# VGA_driver.net
KiCad netlist of a schematic drawn in Altium Designer
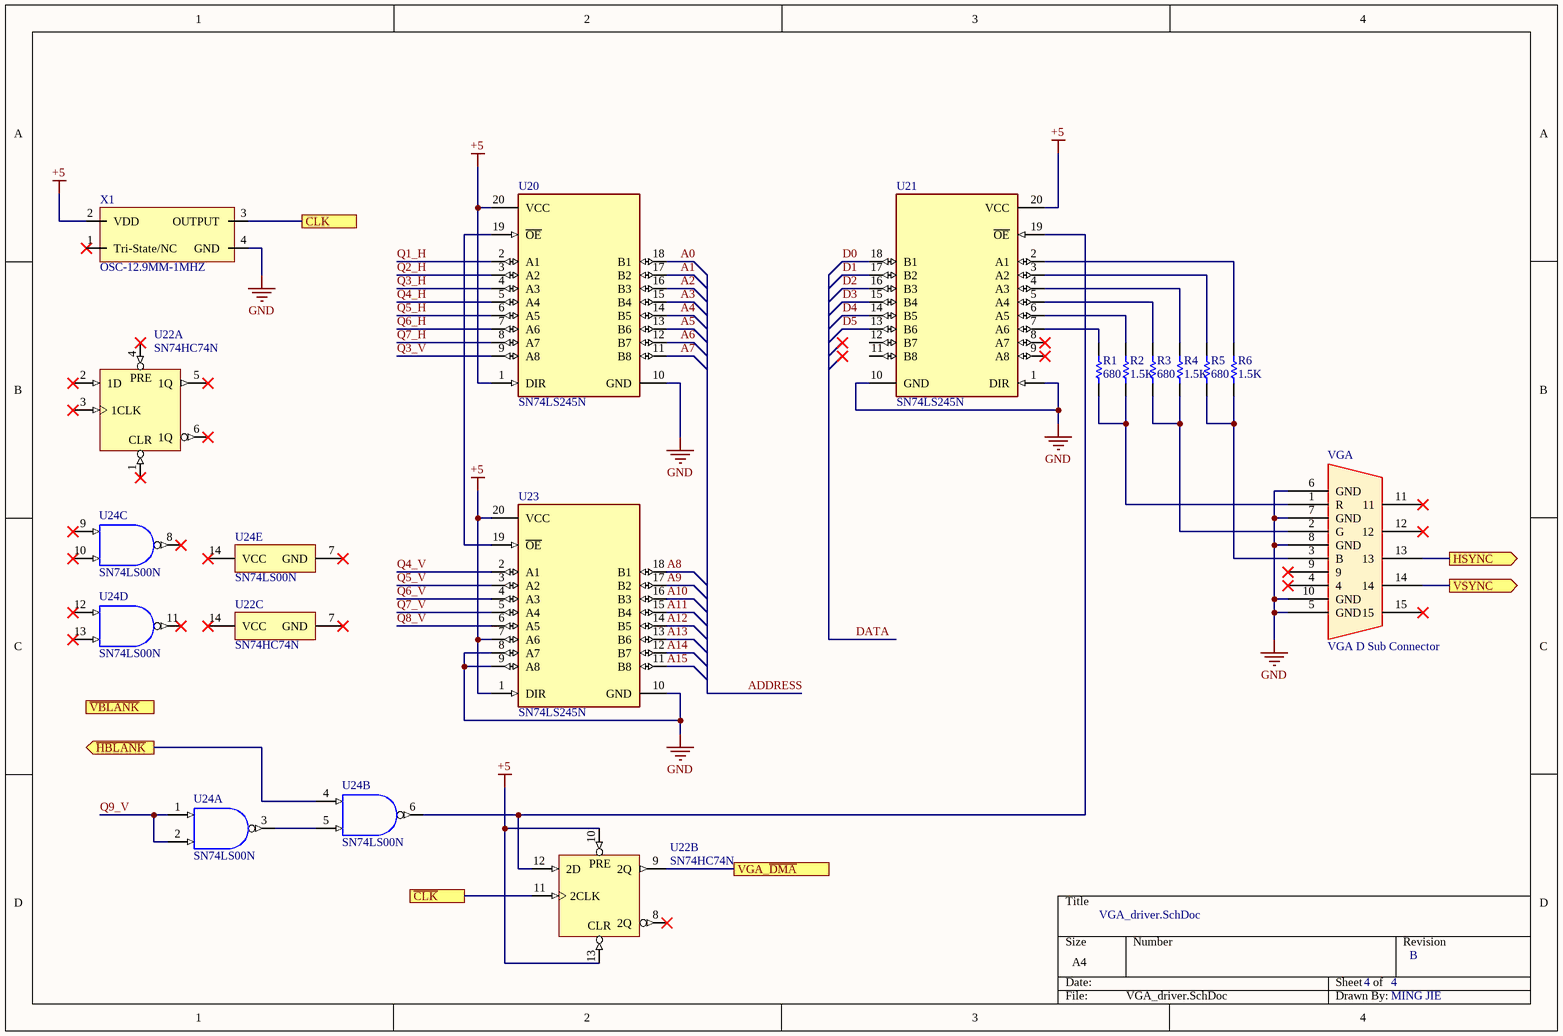
[diagram p0: VGA_driver.SchDoc]

(export (version "E")
  (design (tool "Eeschema 10.0.6"))
  (components
    (comp (ref "R1")
      (value "CRCW0805680RFKEA")
      (footprint "RESC2013X50X30NL20T20")
      (fields (field (name "MANUFACTURER") "Vishay Dale") (field (name "RESISTANCE") "680"))
      (libsource (lib "Altium Content Vault") (part "RES"))
    )
    (comp (ref "R2")
      (value "RC0805FR-071K5L")
      (footprint "RESC2013X60X35LL10T20")
      (description "RES 1.50K OHM 1/8W 1% 0805 SMD")
      (fields (field (name "MANUFACTURER") "Yageo") (field (name "RESISTANCE") "1.5K"))
      (libsource (lib "Altium Content Vault") (part "RES-2"))
    )
    (comp (ref "R3")
      (value "CRCW0805680RFKEA")
      (footprint "RESC2013X50X30NL20T20")
      (fields (field (name "MANUFACTURER") "Vishay Dale") (field (name "RESISTANCE") "680"))
      (libsource (lib "Altium Content Vault") (part "RES"))
    )
    (comp (ref "R4")
      (value "RC0805FR-071K5L")
      (footprint "RESC2013X60X35LL10T20")
      (description "RES 1.50K OHM 1/8W 1% 0805 SMD")
      (fields (field (name "MANUFACTURER") "Yageo") (field (name "RESISTANCE") "1.5K"))
      (libsource (lib "Altium Content Vault") (part "RES-2"))
    )
    (comp (ref "R5")
      (value "CRCW0805680RFKEA")
      (footprint "RESC2013X50X30NL20T20")
      (fields (field (name "MANUFACTURER") "Vishay Dale") (field (name "RESISTANCE") "680"))
      (libsource (lib "Altium Content Vault") (part "RES"))
    )
    (comp (ref "R6")
      (value "RC0805FR-071K5L")
      (footprint "RESC2013X60X35LL10T20")
      (description "RES 1.50K OHM 1/8W 1% 0805 SMD")
      (fields (field (name "MANUFACTURER") "Yageo") (field (name "RESISTANCE") "1.5K"))
      (libsource (lib "Altium Content Vault") (part "RES-2"))
    )
    (comp (ref "U20")
      (value "SN74LS245N")
      (footprint "FP-N0020A-MFG")
      (description "IC TXRX NON-INVERT 5.25V 20DIP")
      (libsource (lib "Altium Content Vault") (part "10c8780e4db4806136f4ae6e668cc9c"))
    )
    (comp (ref "U21")
      (value "SN74LS245N")
      (footprint "FP-N0020A-MFG")
      (description "IC TXRX NON-INVERT 5.25V 20DIP")
      (libsource (lib "") (part "10c8780e4db4806136f4ae6e668cc9c_1"))
    )
    (comp (ref "U22")
      (value "SN74HC74N")
      (footprint "N0014A")
      (description "Dual D-Type Positive-Edge-Triggered Flip-Flops With Clear and Preset, N0014A, TUBE")
      (fields
        (field (name "MANUFACTURER") "Texas Instruments")
        (field (name "GENERIC PART NUMBER") "SN74HC74")
      )
      (libsource (lib "Altium Content Vault") (part "TI-CD_SNX4XXXX74X-14"))
    )
    (comp (ref "U23")
      (value "SN74LS245N")
      (footprint "FP-N0020A-MFG")
      (description "IC TXRX NON-INVERT 5.25V 20DIP")
      (libsource (lib "Altium Content Vault") (part "10c8780e4db4806136f4ae6e668cc9c"))
    )
    (comp (ref "U24")
      (value "SN74LS00N")
      (footprint "N0014A")
      (description "Quad 2-input positive-NAND gates, N0014A, TUBE")
      (fields
        (field (name "MANUFACTURER") "Texas Instruments")
        (field (name "GENERIC PART NUMBER") "SN74LS00")
      )
      (libsource (lib "Altium Content Vault") (part "TI-NAND-4-2IN-14_G"))
    )
    (comp (ref "VGA")
      (value "VGA D Sub Connector")
      (footprint "VGA")
      (libsource (lib "6502_lib") (part "VGA-002"))
    )
    (comp (ref "X1")
      (value "OSC-12.9MM-1MHZ")
      (footprint "OSC_THT_12-9MM")
      (description "12.9MM x 12.9MM, 1MHz Can Oscillator")
      (libsource (lib "6502_lib") (part "OSC-12.9MM-1MHZ"))
    )
  )
  (nets
    (net (code "3") (name "+5") (class "Default")
      (node (ref "U20") (pin "1") (pinfunction "DIR_1") (pintype "input"))
      (node (ref "U20") (pin "20") (pinfunction "VCC_20") (pintype "power_in"))
      (node (ref "U21") (pin "20") (pinfunction "VCC_20") (pintype "power_in"))
      (node (ref "U22") (pin "10") (pinfunction "2~{PRE}_10") (pintype "input"))
      (node (ref "U22") (pin "13") (pinfunction "2~{CLR}_13") (pintype "input"))
      (node (ref "U23") (pin "1") (pinfunction "DIR_1") (pintype "input"))
      (node (ref "U23") (pin "20") (pinfunction "VCC_20") (pintype "power_in"))
      (node (ref "U23") (pin "7") (pinfunction "A6_7") (pintype "bidirectional"))
      (node (ref "X1") (pin "2") (pinfunction "VDD_2") (pintype "passive"))
    )
    (net (code "4") (name "/A0") (class "Default")
      (node (ref "U20") (pin "18") (pinfunction "B1_18") (pintype "bidirectional"))
    )
    (net (code "5") (name "/A1") (class "Default")
      (node (ref "U20") (pin "17") (pinfunction "B2_17") (pintype "bidirectional"))
    )
    (net (code "6") (name "/A2") (class "Default")
      (node (ref "U20") (pin "16") (pinfunction "B3_16") (pintype "bidirectional"))
    )
    (net (code "7") (name "/A3") (class "Default")
      (node (ref "U20") (pin "15") (pinfunction "B4_15") (pintype "bidirectional"))
    )
    (net (code "8") (name "/A4") (class "Default")
      (node (ref "U20") (pin "14") (pinfunction "B5_14") (pintype "bidirectional"))
    )
    (net (code "9") (name "/A5") (class "Default")
      (node (ref "U20") (pin "13") (pinfunction "B6_13") (pintype "bidirectional"))
    )
    (net (code "10") (name "/A6") (class "Default")
      (node (ref "U20") (pin "12") (pinfunction "B7_12") (pintype "bidirectional"))
    )
    (net (code "11") (name "/A7") (class "Default")
      (node (ref "U20") (pin "11") (pinfunction "B8_11") (pintype "bidirectional"))
    )
    (net (code "12") (name "/A8") (class "Default")
      (node (ref "U23") (pin "18") (pinfunction "B1_18") (pintype "bidirectional"))
    )
    (net (code "13") (name "/A9") (class "Default")
      (node (ref "U23") (pin "17") (pinfunction "B2_17") (pintype "bidirectional"))
    )
    (net (code "14") (name "/A10") (class "Default")
      (node (ref "U23") (pin "16") (pinfunction "B3_16") (pintype "bidirectional"))
    )
    (net (code "15") (name "/A11") (class "Default")
      (node (ref "U23") (pin "15") (pinfunction "B4_15") (pintype "bidirectional"))
    )
    (net (code "16") (name "/A12") (class "Default")
      (node (ref "U23") (pin "14") (pinfunction "B5_14") (pintype "bidirectional"))
    )
    (net (code "17") (name "/A13") (class "Default")
      (node (ref "U23") (pin "13") (pinfunction "B6_13") (pintype "bidirectional"))
    )
    (net (code "18") (name "/A14") (class "Default")
      (node (ref "U23") (pin "12") (pinfunction "B7_12") (pintype "bidirectional"))
    )
    (net (code "19") (name "/A15") (class "Default")
      (node (ref "U23") (pin "11") (pinfunction "B8_11") (pintype "bidirectional"))
    )
    (net (code "20") (name "/CLK") (class "Default")
      (node (ref "X1") (pin "3") (pinfunction "OUTPUT_3") (pintype "passive"))
    )
    (net (code "21") (name "/D0") (class "Default")
      (node (ref "U21") (pin "18") (pinfunction "B1_18") (pintype "bidirectional"))
    )
    (net (code "22") (name "/D1") (class "Default")
      (node (ref "U21") (pin "17") (pinfunction "B2_17") (pintype "bidirectional"))
    )
    (net (code "23") (name "/D2") (class "Default")
      (node (ref "U21") (pin "16") (pinfunction "B3_16") (pintype "bidirectional"))
    )
    (net (code "24") (name "/D3") (class "Default")
      (node (ref "U21") (pin "15") (pinfunction "B4_15") (pintype "bidirectional"))
    )
    (net (code "25") (name "/D4") (class "Default")
      (node (ref "U21") (pin "14") (pinfunction "B5_14") (pintype "bidirectional"))
    )
    (net (code "26") (name "/D5") (class "Default")
      (node (ref "U21") (pin "13") (pinfunction "B6_13") (pintype "bidirectional"))
    )
    (net (code "27") (name "/HSYNC") (class "Default")
      (node (ref "VGA") (pin "13") (pinfunction "13_13") (pintype "passive"))
    )
    (net (code "28") (name "/Q1_H") (class "Default")
      (node (ref "U20") (pin "2") (pinfunction "A1_2") (pintype "bidirectional"))
    )
    (net (code "29") (name "/Q2_H") (class "Default")
      (node (ref "U20") (pin "3") (pinfunction "A2_3") (pintype "bidirectional"))
    )
    (net (code "30") (name "/Q3_H") (class "Default")
      (node (ref "U20") (pin "4") (pinfunction "A3_4") (pintype "bidirectional"))
    )
    (net (code "31") (name "/Q3_V") (class "Default")
      (node (ref "U20") (pin "9") (pinfunction "A8_9") (pintype "bidirectional"))
    )
    (net (code "32") (name "/Q4_H") (class "Default")
      (node (ref "U20") (pin "5") (pinfunction "A4_5") (pintype "bidirectional"))
    )
    (net (code "33") (name "/Q4_V") (class "Default")
      (node (ref "U23") (pin "2") (pinfunction "A1_2") (pintype "bidirectional"))
    )
    (net (code "34") (name "/Q5_H") (class "Default")
      (node (ref "U20") (pin "6") (pinfunction "A5_6") (pintype "bidirectional"))
    )
    (net (code "35") (name "/Q5_V") (class "Default")
      (node (ref "U23") (pin "3") (pinfunction "A2_3") (pintype "bidirectional"))
    )
    (net (code "36") (name "/Q6_H") (class "Default")
      (node (ref "U20") (pin "7") (pinfunction "A6_7") (pintype "bidirectional"))
    )
    (net (code "37") (name "/Q6_V") (class "Default")
      (node (ref "U23") (pin "4") (pinfunction "A3_4") (pintype "bidirectional"))
    )
    (net (code "38") (name "/Q7_H") (class "Default")
      (node (ref "U20") (pin "8") (pinfunction "A7_8") (pintype "bidirectional"))
    )
    (net (code "39") (name "/Q7_V") (class "Default")
      (node (ref "U23") (pin "5") (pinfunction "A4_5") (pintype "bidirectional"))
    )
    (net (code "40") (name "/Q8_V") (class "Default")
      (node (ref "U23") (pin "6") (pinfunction "A5_6") (pintype "bidirectional"))
    )
    (net (code "41") (name "/Q9_V") (class "Default")
      (node (ref "U24") (pin "1") (pinfunction "1A_1") (pintype "input"))
      (node (ref "U24") (pin "2") (pinfunction "1B_2") (pintype "input"))
    )
    (net (code "42") (name "/VGA_~{DMA}") (class "Default")
      (node (ref "U22") (pin "9") (pinfunction "2Q_9") (pintype "output"))
    )
    (net (code "43") (name "/VSYNC") (class "Default")
      (node (ref "VGA") (pin "14") (pinfunction "14_14") (pintype "passive"))
    )
    (net (code "46") (name "/~{CLK}") (class "Default")
      (node (ref "U22") (pin "11") (pinfunction "2CLK_11") (pintype "input"))
    )
    (net (code "47") (name "/~{HBLANK}") (class "Default")
      (node (ref "U24") (pin "4") (pinfunction "2A_4") (pintype "input"))
    )
    (net (code "49") (name "GND") (class "Default")
      (node (ref "U20") (pin "10") (pinfunction "GND_10") (pintype "power_in"))
      (node (ref "U21") (pin "1") (pinfunction "DIR_1") (pintype "input"))
      (node (ref "U21") (pin "10") (pinfunction "GND_10") (pintype "power_in"))
      (node (ref "U23") (pin "10") (pinfunction "GND_10") (pintype "power_in"))
      (node (ref "U23") (pin "8") (pinfunction "A7_8") (pintype "bidirectional"))
      (node (ref "U23") (pin "9") (pinfunction "A8_9") (pintype "bidirectional"))
      (node (ref "VGA") (pin "10") (pinfunction "GND_10") (pintype "passive"))
      (node (ref "VGA") (pin "5") (pinfunction "GND_5") (pintype "passive"))
      (node (ref "VGA") (pin "6") (pinfunction "GND_6") (pintype "passive"))
      (node (ref "VGA") (pin "7") (pinfunction "GND_7") (pintype "passive"))
      (node (ref "VGA") (pin "8") (pinfunction "GND_8") (pintype "passive"))
      (node (ref "X1") (pin "4") (pinfunction "GND_4") (pintype "passive"))
    )
    (net (code "50") (name "Net-(U20-~{OE})") (class "Default")
      (node (ref "U20") (pin "19") (pinfunction "~{OE}_19") (pintype "input"))
      (node (ref "U23") (pin "19") (pinfunction "~{OE}_19") (pintype "input"))
    )
    (net (code "51") (name "Net-(U21-A1)") (class "Default")
      (node (ref "R6") (pin "2") (pinfunction "2_2") (pintype "passive"))
      (node (ref "U21") (pin "2") (pinfunction "A1_2") (pintype "bidirectional"))
    )
    (net (code "52") (name "Net-(U21-A2)") (class "Default")
      (node (ref "R5") (pin "2") (pinfunction "2_2") (pintype "passive"))
      (node (ref "U21") (pin "3") (pinfunction "A2_3") (pintype "bidirectional"))
    )
    (net (code "53") (name "Net-(U21-A3)") (class "Default")
      (node (ref "R4") (pin "2") (pinfunction "2_2") (pintype "passive"))
      (node (ref "U21") (pin "4") (pinfunction "A3_4") (pintype "bidirectional"))
    )
    (net (code "54") (name "Net-(U21-A4)") (class "Default")
      (node (ref "R3") (pin "2") (pinfunction "2_2") (pintype "passive"))
      (node (ref "U21") (pin "5") (pinfunction "A4_5") (pintype "bidirectional"))
    )
    (net (code "55") (name "Net-(U21-A5)") (class "Default")
      (node (ref "R2") (pin "2") (pinfunction "2_2") (pintype "passive"))
      (node (ref "U21") (pin "6") (pinfunction "A5_6") (pintype "bidirectional"))
    )
    (net (code "56") (name "Net-(U21-A6)") (class "Default")
      (node (ref "R1") (pin "2") (pinfunction "2_2") (pintype "passive"))
      (node (ref "U21") (pin "7") (pinfunction "A6_7") (pintype "bidirectional"))
    )
    (net (code "57") (name "Net-(U21-~{OE})") (class "Default")
      (node (ref "U21") (pin "19") (pinfunction "~{OE}_19") (pintype "input"))
      (node (ref "U22") (pin "12") (pinfunction "2D_12") (pintype "input"))
      (node (ref "U24") (pin "6") (pinfunction "2Y_6") (pintype "output"))
    )
    (net (code "58") (name "Net-(U24A-1Y)") (class "Default")
      (node (ref "U24") (pin "3") (pinfunction "1Y_3") (pintype "output"))
      (node (ref "U24") (pin "5") (pinfunction "2B_5") (pintype "input"))
    )
    (net (code "59") (name "Net-(VGA-B)") (class "Default")
      (node (ref "R5") (pin "1") (pinfunction "1_1") (pintype "passive"))
      (node (ref "R6") (pin "1") (pinfunction "1_1") (pintype "passive"))
      (node (ref "VGA") (pin "3") (pinfunction "B_3") (pintype "passive"))
    )
    (net (code "60") (name "Net-(VGA-G)") (class "Default")
      (node (ref "R3") (pin "1") (pinfunction "1_1") (pintype "passive"))
      (node (ref "R4") (pin "1") (pinfunction "1_1") (pintype "passive"))
      (node (ref "VGA") (pin "2") (pinfunction "G_2") (pintype "passive"))
    )
    (net (code "61") (name "Net-(VGA-R)") (class "Default")
      (node (ref "R1") (pin "1") (pinfunction "1_1") (pintype "passive"))
      (node (ref "R2") (pin "1") (pinfunction "1_1") (pintype "passive"))
      (node (ref "VGA") (pin "1") (pinfunction "R_1") (pintype "passive"))
    )
    (net (code "62") (name "unconnected-(U21-A7-Pad8)") (class "Default")
      (node (ref "U21") (pin "8") (pinfunction "A7_8") (pintype "bidirectional+no_connect"))
    )
    (net (code "63") (name "unconnected-(U21-A8-Pad9)") (class "Default")
      (node (ref "U21") (pin "9") (pinfunction "A8_9") (pintype "bidirectional+no_connect"))
    )
    (net (code "64") (name "unconnected-(U21-B7-Pad12)") (class "Default")
      (node (ref "U21") (pin "12") (pinfunction "B7_12") (pintype "bidirectional"))
    )
    (net (code "65") (name "unconnected-(U21-B8-Pad11)") (class "Default")
      (node (ref "U21") (pin "11") (pinfunction "B8_11") (pintype "bidirectional"))
    )
    (net (code "66") (name "unconnected-(U22A-1CLK-Pad3)") (class "Default")
      (node (ref "U22") (pin "3") (pinfunction "1CLK_3") (pintype "input+no_connect"))
    )
    (net (code "67") (name "unconnected-(U22A-1D-Pad2)") (class "Default")
      (node (ref "U22") (pin "2") (pinfunction "1D_2") (pintype "input+no_connect"))
    )
    (net (code "68") (name "unconnected-(U22A-1Q-Pad5)") (class "Default")
      (node (ref "U22") (pin "5") (pinfunction "1Q_5") (pintype "output+no_connect"))
    )
    (net (code "69") (name "unconnected-(U22A-1Q-Pad6)") (class "Default")
      (node (ref "U22") (pin "6") (pinfunction "1Q_6") (pintype "output+no_connect"))
    )
    (net (code "70") (name "unconnected-(U22A-1~{CLR}-Pad1)") (class "Default")
      (node (ref "U22") (pin "1") (pinfunction "1~{CLR}_1") (pintype "input+no_connect"))
    )
    (net (code "71") (name "unconnected-(U22A-1~{PRE}-Pad4)") (class "Default")
      (node (ref "U22") (pin "4") (pinfunction "1~{PRE}_4") (pintype "input+no_connect"))
    )
    (net (code "72") (name "unconnected-(U22B-2Q-Pad8)") (class "Default")
      (node (ref "U22") (pin "8") (pinfunction "2Q_8") (pintype "output+no_connect"))
    )
    (net (code "73") (name "unconnected-(U22C-GND-Pad7)") (class "Default")
      (node (ref "U22") (pin "7") (pinfunction "GND_7") (pintype "power_in+no_connect"))
    )
    (net (code "74") (name "unconnected-(U22C-VCC-Pad14)") (class "Default")
      (node (ref "U22") (pin "14") (pinfunction "VCC_14") (pintype "power_in+no_connect"))
    )
    (net (code "75") (name "unconnected-(U24C-3A-Pad9)") (class "Default")
      (node (ref "U24") (pin "9") (pinfunction "3A_9") (pintype "input+no_connect"))
    )
    (net (code "76") (name "unconnected-(U24C-3B-Pad10)") (class "Default")
      (node (ref "U24") (pin "10") (pinfunction "3B_10") (pintype "input+no_connect"))
    )
    (net (code "77") (name "unconnected-(U24C-3Y-Pad8)") (class "Default")
      (node (ref "U24") (pin "8") (pinfunction "3Y_8") (pintype "output+no_connect"))
    )
    (net (code "78") (name "unconnected-(U24D-4A-Pad12)") (class "Default")
      (node (ref "U24") (pin "12") (pinfunction "4A_12") (pintype "input+no_connect"))
    )
    (net (code "79") (name "unconnected-(U24D-4B-Pad13)") (class "Default")
      (node (ref "U24") (pin "13") (pinfunction "4B_13") (pintype "input+no_connect"))
    )
    (net (code "80") (name "unconnected-(U24D-4Y-Pad11)") (class "Default")
      (node (ref "U24") (pin "11") (pinfunction "4Y_11") (pintype "output+no_connect"))
    )
    (net (code "81") (name "unconnected-(U24E-GND-Pad7)") (class "Default")
      (node (ref "U24") (pin "7") (pinfunction "GND_7") (pintype "power_in+no_connect"))
    )
    (net (code "82") (name "unconnected-(U24E-VCC-Pad14)") (class "Default")
      (node (ref "U24") (pin "14") (pinfunction "VCC_14") (pintype "power_in+no_connect"))
    )
    (net (code "83") (name "unconnected-(VGA-Pad4)") (class "Default")
      (node (ref "VGA") (pin "4") (pinfunction "4_4") (pintype "passive+no_connect"))
    )
    (net (code "84") (name "unconnected-(VGA-Pad9)") (class "Default")
      (node (ref "VGA") (pin "9") (pinfunction "9_9") (pintype "passive+no_connect"))
    )
    (net (code "85") (name "unconnected-(VGA-Pad11)") (class "Default")
      (node (ref "VGA") (pin "11") (pinfunction "11_11") (pintype "passive+no_connect"))
    )
    (net (code "86") (name "unconnected-(VGA-Pad12)") (class "Default")
      (node (ref "VGA") (pin "12") (pinfunction "12_12") (pintype "passive+no_connect"))
    )
    (net (code "87") (name "unconnected-(VGA-Pad15)") (class "Default")
      (node (ref "VGA") (pin "15") (pinfunction "15_15") (pintype "passive+no_connect"))
    )
    (net (code "88") (name "unconnected-(X1-Tri-State{slash}NC-Pad1)") (class "Default")
      (node (ref "X1") (pin "1") (pinfunction "Tri-State/NC_1") (pintype "passive+no_connect"))
    )
  )
)
